# rx.net
KiCad netlist of a schematic drawn in EAGLE
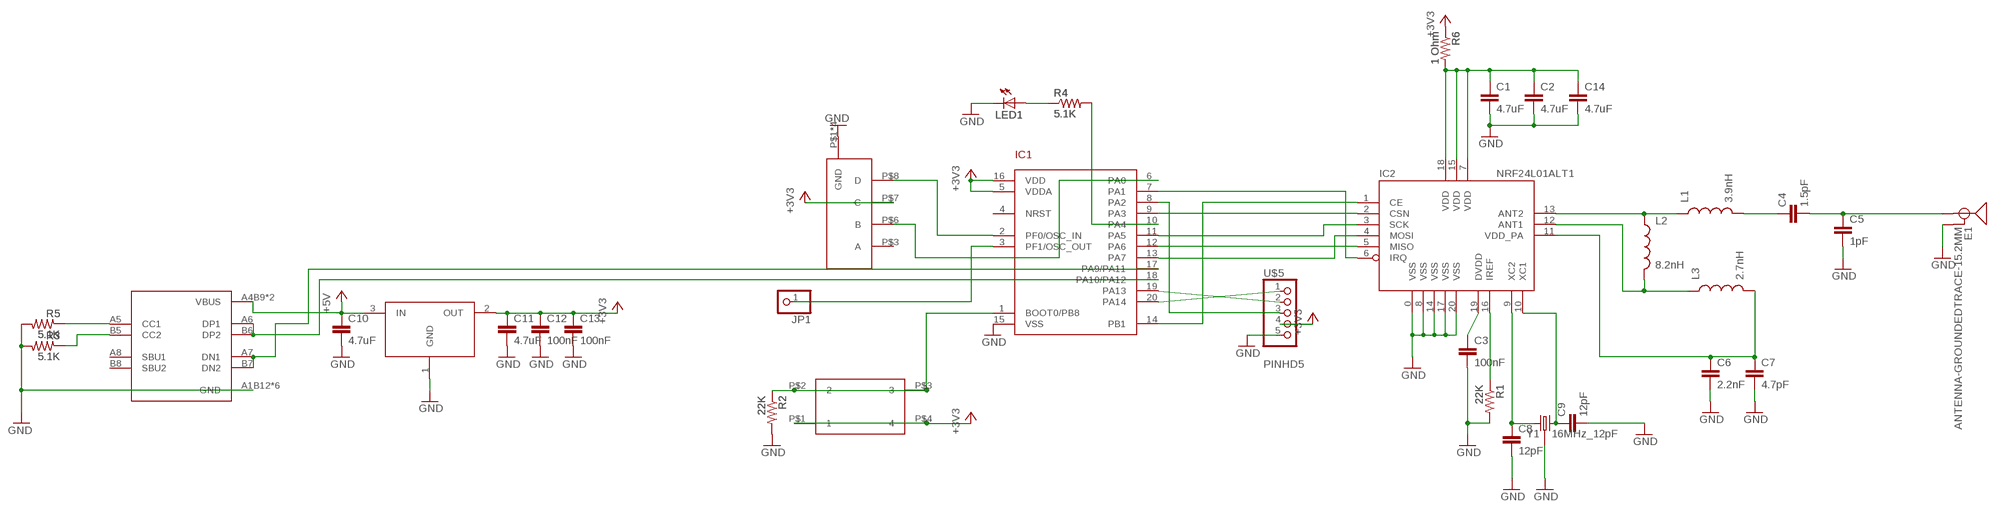
[diagram p0: schematic, sheet 1]

(export (version "E")
  (design (tool "Eeschema 10.0.6"))
  (components
    (comp (ref "C1")
      (value "4.7uF")
      (footprint "eagle-import:0805")
      (libsource (lib "eagle-import") (part "CAP0805"))
    )
    (comp (ref "C2")
      (value "4.7uF")
      (footprint "eagle-import:0805")
      (libsource (lib "eagle-import") (part "CAP0805"))
    )
    (comp (ref "C3")
      (value "100nF")
      (footprint "eagle-import:0805")
      (libsource (lib "eagle-import") (part "CAP0805"))
    )
    (comp (ref "C4")
      (value "1.5pF")
      (footprint "eagle-import:0805")
      (libsource (lib "eagle-import") (part "CAP0805"))
    )
    (comp (ref "C5")
      (value "1pF")
      (footprint "eagle-import:0805")
      (libsource (lib "eagle-import") (part "CAP0805"))
    )
    (comp (ref "C6")
      (value "2.2nF")
      (footprint "eagle-import:0805")
      (libsource (lib "eagle-import") (part "CAP0805"))
    )
    (comp (ref "C7")
      (value "4.7pF")
      (footprint "eagle-import:0805")
      (libsource (lib "eagle-import") (part "CAP0805"))
    )
    (comp (ref "C8")
      (value "12pF")
      (footprint "eagle-import:0805")
      (libsource (lib "eagle-import") (part "CAP0805"))
    )
    (comp (ref "C9")
      (value "12pF")
      (footprint "eagle-import:0805")
      (libsource (lib "eagle-import") (part "CAP0805"))
    )
    (comp (ref "C10")
      (value "4.7uF")
      (footprint "eagle-import:0805")
      (libsource (lib "eagle-import") (part "CAP0805"))
    )
    (comp (ref "C11")
      (value "4.7uF")
      (footprint "eagle-import:0805")
      (libsource (lib "eagle-import") (part "CAP0805"))
    )
    (comp (ref "C12")
      (value "100nF")
      (footprint "eagle-import:0805")
      (libsource (lib "eagle-import") (part "CAP0805"))
    )
    (comp (ref "C13")
      (value "100nF")
      (footprint "eagle-import:0805")
      (libsource (lib "eagle-import") (part "CAP0805"))
    )
    (comp (ref "C14")
      (value "4.7uF")
      (footprint "eagle-import:0805")
      (libsource (lib "eagle-import") (part "CAP0805"))
    )
    (comp (ref "E1")
      (value "ANTENNA-GROUNDEDTRACE-15.2MM")
      (footprint "eagle-import:TRACE_ANTENNA_2.4GHZ_15.2MM")
      (libsource (lib "eagle-import") (part "ANTENNA-GROUNDEDTRACE-15.2MM"))
    )
    (comp (ref "IC1")
      (value "STM32F042F4")
      (footprint "eagle-import:TSSOP20")
      (libsource (lib "eagle-import") (part "STM32F042F4"))
    )
    (comp (ref "IC2")
      (value "NRF24L01ALT1")
      (footprint "eagle-import:QFN20_ALT1")
      (libsource (lib "eagle-import") (part "NRF24L01ALT1"))
    )
    (comp (ref "JP1")
      (value "PINHD-1X1CB")
      (footprint "eagle-import:1X01-CLEANBIG")
      (libsource (lib "eagle-import") (part "PINHD-1X1CB"))
    )
    (comp (ref "L1")
      (value "3.9nH")
      (footprint "eagle-import:0805")
      (libsource (lib "eagle-import") (part "INDUCTOR0805"))
    )
    (comp (ref "L2")
      (value "8.2nH")
      (footprint "eagle-import:0805")
      (libsource (lib "eagle-import") (part "INDUCTOR0805"))
    )
    (comp (ref "L3")
      (value "2.7nH")
      (footprint "eagle-import:0805")
      (libsource (lib "eagle-import") (part "INDUCTOR0805"))
    )
    (comp (ref "LED1")
      (value "LEDCHIP-LED0805")
      (footprint "eagle-import:CHIP-LED0805")
      (libsource (lib "eagle-import") (part "LEDCHIP-LED0805"))
    )
    (comp (ref "R1")
      (value "22K")
      (footprint "eagle-import:0805")
      (libsource (lib "eagle-import") (part "RESISTOR0805-RES"))
    )
    (comp (ref "R2")
      (value "22K")
      (footprint "eagle-import:0805")
      (libsource (lib "eagle-import") (part "RESISTOR0805-RES"))
    )
    (comp (ref "R3")
      (value "5.1K")
      (footprint "eagle-import:0805")
      (libsource (lib "eagle-import") (part "RESISTOR0805-RES"))
    )
    (comp (ref "R4")
      (value "5.1K")
      (footprint "eagle-import:0805")
      (libsource (lib "eagle-import") (part "RESISTOR0805-RES"))
    )
    (comp (ref "R5")
      (value "5.1K")
      (footprint "eagle-import:0805")
      (libsource (lib "eagle-import") (part "RESISTOR0805-RES"))
    )
    (comp (ref "R6")
      (value "1 Ohm")
      (footprint "eagle-import:0805")
      (libsource (lib "eagle-import") (part "RESISTOR0805-RES"))
    )
    (comp (ref "SW1")
      (value "SW_3POS_DEVSW_3POS_OFFICIAL")
      (footprint "eagle-import:SW_3POS_FOOT_OFFICIAL")
      (libsource (lib "eagle-import") (part "SW_3POS_DEVSW_3POS_OFFICIAL"))
    )
    (comp (ref "SW2")
      (value "324_SW324_SWITCH_FOOT_HOLE")
      (footprint "eagle-import:342_SWICH_FOOT_HOLE")
      (libsource (lib "eagle-import") (part "324_SW324_SWITCH_FOOT_HOLE"))
    )
    (comp (ref "U$5")
      (value "PINHD5")
      (footprint "eagle-import:1X05")
      (libsource (lib "eagle-import") (part "PINHD5"))
    )
    (comp (ref "U1")
      (value "USBC_16P")
      (footprint "eagle-import:USBC_16P_FOOT")
      (libsource (lib "eagle-import") (part "USBC_16P"))
    )
    (comp (ref "U2")
      (value "XC6206_DEV")
      (footprint "eagle-import:SOT23R_INFINEON")
      (libsource (lib "eagle-import") (part "XC6206_DEV"))
    )
    (comp (ref "Y1")
      (value "16MHz_12pF")
      (footprint "eagle-import:CRYSTAL-SMD-3.2X2.5MM")
      (libsource (lib "eagle-import") (part "CRYSTAL-26MHZSMD-3.2X2.5"))
    )
  )
  (nets
    (net (code "1") (name "+3V3") (class "Default")
      (node (ref "C11") (pin "1") (pinfunction "1_1") (pintype "passive"))
      (node (ref "C12") (pin "1") (pinfunction "1_1") (pintype "passive"))
      (node (ref "C13") (pin "1") (pinfunction "1_1") (pintype "passive"))
      (node (ref "IC1") (pin "16") (pinfunction "VDD_16") (pintype "bidirectional"))
      (node (ref "IC1") (pin "5") (pinfunction "VDDA_5") (pintype "bidirectional"))
      (node (ref "R6") (pin "1") (pinfunction "1_1") (pintype "passive"))
      (node (ref "SW1") (pin "P$7") (pinfunction "C_P$7") (pintype "bidirectional"))
      (node (ref "SW2") (pin "P$1") (pinfunction "1_P$1") (pintype "bidirectional"))
      (node (ref "SW2") (pin "P$4") (pinfunction "4_P$4") (pintype "bidirectional"))
      (node (ref "U$5") (pin "4") (pinfunction "4_4") (pintype "passive"))
      (node (ref "U2") (pin "2") (pinfunction "OUT_2") (pintype "bidirectional"))
    )
    (net (code "2") (name "+5V") (class "Default")
      (node (ref "C10") (pin "1") (pinfunction "1_1") (pintype "passive"))
      (node (ref "U1") (pin "A4B9") (pinfunction "VBUS_A4B9") (pintype "bidirectional"))
      (node (ref "U1") (pin "B4A9") (pinfunction "VBUS_B4A9") (pintype "bidirectional"))
      (node (ref "U2") (pin "3") (pinfunction "IN_3") (pintype "bidirectional"))
    )
    (net (code "3") (name "GND") (class "Default")
      (node (ref "C1") (pin "2") (pinfunction "2_2") (pintype "passive"))
      (node (ref "C10") (pin "2") (pinfunction "2_2") (pintype "passive"))
      (node (ref "C11") (pin "2") (pinfunction "2_2") (pintype "passive"))
      (node (ref "C12") (pin "2") (pinfunction "2_2") (pintype "passive"))
      (node (ref "C13") (pin "2") (pinfunction "2_2") (pintype "passive"))
      (node (ref "C14") (pin "2") (pinfunction "2_2") (pintype "passive"))
      (node (ref "C2") (pin "2") (pinfunction "2_2") (pintype "passive"))
      (node (ref "C3") (pin "2") (pinfunction "2_2") (pintype "passive"))
      (node (ref "C5") (pin "2") (pinfunction "2_2") (pintype "passive"))
      (node (ref "C6") (pin "2") (pinfunction "2_2") (pintype "passive"))
      (node (ref "C7") (pin "2") (pinfunction "2_2") (pintype "passive"))
      (node (ref "C8") (pin "2") (pinfunction "2_2") (pintype "passive"))
      (node (ref "C9") (pin "2") (pinfunction "2_2") (pintype "passive"))
      (node (ref "E1") (pin "GND") (pinfunction "GND_GND") (pintype "bidirectional"))
      (node (ref "IC1") (pin "15") (pinfunction "VSS_15") (pintype "bidirectional"))
      (node (ref "IC2") (pin "0") (pinfunction "VSS_0") (pintype "power_in"))
      (node (ref "IC2") (pin "14") (pinfunction "VSS_14") (pintype "power_in"))
      (node (ref "IC2") (pin "17") (pinfunction "VSS_17") (pintype "power_in"))
      (node (ref "IC2") (pin "20") (pinfunction "VSS_20") (pintype "power_in"))
      (node (ref "IC2") (pin "8") (pinfunction "VSS_8") (pintype "power_in"))
      (node (ref "LED1") (pin "C") (pinfunction "C_C") (pintype "passive"))
      (node (ref "R1") (pin "2") (pinfunction "2_2") (pintype "passive"))
      (node (ref "R2") (pin "2") (pinfunction "2_2") (pintype "passive"))
      (node (ref "R3") (pin "2") (pinfunction "2_2") (pintype "passive"))
      (node (ref "R5") (pin "2") (pinfunction "2_2") (pintype "passive"))
      (node (ref "SW1") (pin "P$1") (pinfunction "GND_P$1") (pintype "bidirectional"))
      (node (ref "SW1") (pin "P$2") (pinfunction "GND_P$2") (pintype "bidirectional"))
      (node (ref "SW1") (pin "P$4") (pinfunction "GND_P$4") (pintype "bidirectional"))
      (node (ref "SW1") (pin "P$5") (pinfunction "GND_P$5") (pintype "bidirectional"))
      (node (ref "U$5") (pin "5") (pinfunction "5_5") (pintype "passive"))
      (node (ref "U1") (pin "A1B12") (pinfunction "GND_A1B12") (pintype "bidirectional"))
      (node (ref "U1") (pin "B11A12") (pinfunction "GND_B11A12") (pintype "bidirectional"))
      (node (ref "U1") (pin "P$13") (pinfunction "GND_P$13") (pintype "bidirectional"))
      (node (ref "U1") (pin "P$14") (pinfunction "GND_P$14") (pintype "bidirectional"))
      (node (ref "U1") (pin "P$15") (pinfunction "GND_P$15") (pintype "bidirectional"))
      (node (ref "U1") (pin "P$16") (pinfunction "GND_P$16") (pintype "bidirectional"))
      (node (ref "U2") (pin "1") (pinfunction "GND_1") (pintype "bidirectional"))
      (node (ref "Y1") (pin "2") (pinfunction "3_2") (pintype "passive"))
      (node (ref "Y1") (pin "4") (pinfunction "3_4") (pintype "passive"))
    )
    (net (code "4") (name "Net-(C1-Pad1)") (class "Default")
      (node (ref "C1") (pin "1") (pinfunction "1_1") (pintype "passive"))
      (node (ref "C14") (pin "1") (pinfunction "1_1") (pintype "passive"))
      (node (ref "C2") (pin "1") (pinfunction "1_1") (pintype "passive"))
      (node (ref "IC2") (pin "15") (pinfunction "VDD_15") (pintype "power_in"))
      (node (ref "IC2") (pin "18") (pinfunction "VDD_18") (pintype "power_in"))
      (node (ref "IC2") (pin "7") (pinfunction "VDD_7") (pintype "power_in"))
      (node (ref "R6") (pin "2") (pinfunction "2_2") (pintype "passive"))
    )
    (net (code "5") (name "Net-(C4-Pad1)") (class "Default")
      (node (ref "C4") (pin "1") (pinfunction "1_1") (pintype "passive"))
      (node (ref "L1") (pin "2") (pinfunction "2_2") (pintype "passive"))
    )
    (net (code "6") (name "Net-(E1-SIGNAL)") (class "Default")
      (node (ref "C4") (pin "2") (pinfunction "2_2") (pintype "passive"))
      (node (ref "C5") (pin "1") (pinfunction "1_1") (pintype "passive"))
      (node (ref "E1") (pin "ANT") (pinfunction "SIGNAL_ANT") (pintype "bidirectional"))
    )
    (net (code "7") (name "Net-(IC1-BOOT0{slash}PB8)") (class "Default")
      (node (ref "IC1") (pin "1") (pinfunction "BOOT0/PB8_1") (pintype "bidirectional"))
      (node (ref "R2") (pin "1") (pinfunction "1_1") (pintype "passive"))
      (node (ref "SW2") (pin "P$2") (pinfunction "2_P$2") (pintype "bidirectional"))
      (node (ref "SW2") (pin "P$3") (pinfunction "3_P$3") (pintype "bidirectional"))
    )
    (net (code "8") (name "Net-(IC1-PA0)") (class "Default")
      (node (ref "IC1") (pin "6") (pinfunction "PA0_6") (pintype "bidirectional"))
      (node (ref "SW1") (pin "P$6") (pinfunction "B_P$6") (pintype "bidirectional"))
    )
    (net (code "9") (name "Net-(IC1-PA1)") (class "Default")
      (node (ref "IC1") (pin "7") (pinfunction "PA1_7") (pintype "bidirectional"))
      (node (ref "IC2") (pin "6") (pinfunction "IRQ_6") (pintype "output"))
    )
    (net (code "10") (name "Net-(IC1-PA2)") (class "Default")
      (node (ref "IC1") (pin "8") (pinfunction "PA2_8") (pintype "bidirectional"))
      (node (ref "U$5") (pin "3") (pinfunction "3_3") (pintype "passive"))
    )
    (net (code "11") (name "Net-(IC1-PA3)") (class "Default")
      (node (ref "IC1") (pin "9") (pinfunction "PA3_9") (pintype "bidirectional"))
      (node (ref "IC2") (pin "2") (pinfunction "CSN_2") (pintype "input"))
    )
    (net (code "12") (name "Net-(IC1-PA4)") (class "Default")
      (node (ref "IC1") (pin "10") (pinfunction "PA4_10") (pintype "bidirectional"))
      (node (ref "R4") (pin "2") (pinfunction "2_2") (pintype "passive"))
    )
    (net (code "13") (name "Net-(IC1-PA5)") (class "Default")
      (node (ref "IC1") (pin "11") (pinfunction "PA5_11") (pintype "bidirectional"))
      (node (ref "IC2") (pin "3") (pinfunction "SCK_3") (pintype "input"))
    )
    (net (code "14") (name "Net-(IC1-PA6)") (class "Default")
      (node (ref "IC1") (pin "12") (pinfunction "PA6_12") (pintype "bidirectional"))
      (node (ref "IC2") (pin "5") (pinfunction "MISO_5") (pintype "output"))
    )
    (net (code "15") (name "Net-(IC1-PA7)") (class "Default")
      (node (ref "IC1") (pin "13") (pinfunction "PA7_13") (pintype "bidirectional"))
      (node (ref "IC2") (pin "4") (pinfunction "MOSI_4") (pintype "input"))
    )
    (net (code "16") (name "Net-(IC1-PA9{slash}PA11)") (class "Default")
      (node (ref "IC1") (pin "17") (pinfunction "PA9/PA11_17") (pintype "bidirectional"))
      (node (ref "U1") (pin "A7") (pinfunction "DN1_A7") (pintype "bidirectional"))
      (node (ref "U1") (pin "B7") (pinfunction "DN2_B7") (pintype "bidirectional"))
    )
    (net (code "17") (name "Net-(IC1-PA10{slash}PA12)") (class "Default")
      (node (ref "IC1") (pin "18") (pinfunction "PA10/PA12_18") (pintype "bidirectional"))
      (node (ref "U1") (pin "A6") (pinfunction "DP1_A6") (pintype "bidirectional"))
      (node (ref "U1") (pin "B6") (pinfunction "DP2_B6") (pintype "bidirectional"))
    )
    (net (code "18") (name "Net-(IC1-PA13)") (class "Default")
      (node (ref "IC1") (pin "19") (pinfunction "PA13_19") (pintype "bidirectional"))
      (node (ref "U$5") (pin "2") (pinfunction "2_2") (pintype "passive"))
    )
    (net (code "19") (name "Net-(IC1-PA14)") (class "Default")
      (node (ref "IC1") (pin "20") (pinfunction "PA14_20") (pintype "bidirectional"))
      (node (ref "U$5") (pin "1") (pinfunction "1_1") (pintype "passive"))
    )
    (net (code "20") (name "Net-(IC1-PB1)") (class "Default")
      (node (ref "IC1") (pin "14") (pinfunction "PB1_14") (pintype "bidirectional"))
      (node (ref "IC2") (pin "1") (pinfunction "CE_1") (pintype "input"))
    )
    (net (code "21") (name "Net-(IC1-PF0{slash}OSC_IN)") (class "Default")
      (node (ref "IC1") (pin "2") (pinfunction "PF0/OSC_IN_2") (pintype "bidirectional"))
      (node (ref "SW1") (pin "P$8") (pinfunction "D_P$8") (pintype "bidirectional"))
    )
    (net (code "22") (name "Net-(IC1-PF1{slash}OSC_OUT)") (class "Default")
      (node (ref "IC1") (pin "3") (pinfunction "PF1/OSC_OUT_3") (pintype "bidirectional"))
      (node (ref "JP1") (pin "1") (pinfunction "1_1") (pintype "passive"))
    )
    (net (code "23") (name "Net-(IC2-ANT1)") (class "Default")
      (node (ref "IC2") (pin "12") (pinfunction "ANT1_12") (pintype "output"))
      (node (ref "L2") (pin "2") (pinfunction "2_2") (pintype "passive"))
      (node (ref "L3") (pin "1") (pinfunction "1_1") (pintype "passive"))
    )
    (net (code "24") (name "Net-(IC2-ANT2)") (class "Default")
      (node (ref "IC2") (pin "13") (pinfunction "ANT2_13") (pintype "output"))
      (node (ref "L1") (pin "1") (pinfunction "1_1") (pintype "passive"))
      (node (ref "L2") (pin "1") (pinfunction "1_1") (pintype "passive"))
    )
    (net (code "25") (name "Net-(IC2-DVDD)") (class "Default")
      (node (ref "C3") (pin "1") (pinfunction "1_1") (pintype "passive"))
      (node (ref "IC2") (pin "19") (pinfunction "DVDD_19") (pintype "power_in"))
    )
    (net (code "26") (name "Net-(IC2-IREF)") (class "Default")
      (node (ref "IC2") (pin "16") (pinfunction "IREF_16") (pintype "input"))
      (node (ref "R1") (pin "1") (pinfunction "1_1") (pintype "passive"))
    )
    (net (code "27") (name "Net-(IC2-VDD_PA)") (class "Default")
      (node (ref "C6") (pin "1") (pinfunction "1_1") (pintype "passive"))
      (node (ref "C7") (pin "1") (pinfunction "1_1") (pintype "passive"))
      (node (ref "IC2") (pin "11") (pinfunction "VDD_PA_11") (pintype "power_in"))
      (node (ref "L3") (pin "2") (pinfunction "2_2") (pintype "passive"))
    )
    (net (code "28") (name "Net-(IC2-XC1)") (class "Default")
      (node (ref "C9") (pin "1") (pinfunction "1_1") (pintype "passive"))
      (node (ref "IC2") (pin "10") (pinfunction "XC1_10") (pintype "input"))
      (node (ref "Y1") (pin "3") (pinfunction "2_3") (pintype "passive"))
    )
    (net (code "29") (name "Net-(IC2-XC2)") (class "Default")
      (node (ref "C8") (pin "1") (pinfunction "1_1") (pintype "passive"))
      (node (ref "IC2") (pin "9") (pinfunction "XC2_9") (pintype "input"))
      (node (ref "Y1") (pin "1") (pinfunction "1_1") (pintype "passive"))
    )
    (net (code "30") (name "Net-(LED1-PadA)") (class "Default")
      (node (ref "LED1") (pin "A") (pinfunction "A_A") (pintype "passive"))
      (node (ref "R4") (pin "1") (pinfunction "1_1") (pintype "passive"))
    )
    (net (code "31") (name "Net-(U1-CC1)") (class "Default")
      (node (ref "R5") (pin "1") (pinfunction "1_1") (pintype "passive"))
      (node (ref "U1") (pin "A5") (pinfunction "CC1_A5") (pintype "bidirectional"))
    )
    (net (code "32") (name "Net-(U1-CC2)") (class "Default")
      (node (ref "R3") (pin "1") (pinfunction "1_1") (pintype "passive"))
      (node (ref "U1") (pin "B5") (pinfunction "CC2_B5") (pintype "bidirectional"))
    )
    (net (code "33") (name "unconnected-(IC1-NRST-Pad4)") (class "Default")
      (node (ref "IC1") (pin "4") (pinfunction "NRST_4") (pintype "bidirectional"))
    )
    (net (code "34") (name "unconnected-(SW1-A-PadP$3)") (class "Default")
      (node (ref "SW1") (pin "P$3") (pinfunction "A_P$3") (pintype "bidirectional"))
    )
    (net (code "35") (name "unconnected-(U1-SBU1-PadA8)") (class "Default")
      (node (ref "U1") (pin "A8") (pinfunction "SBU1_A8") (pintype "bidirectional"))
    )
    (net (code "36") (name "unconnected-(U1-SBU2-PadB8)") (class "Default")
      (node (ref "U1") (pin "B8") (pinfunction "SBU2_B8") (pintype "bidirectional"))
    )
  )
)
